# Schematic.net
KiCad netlist of a schematic drawn in EAGLE
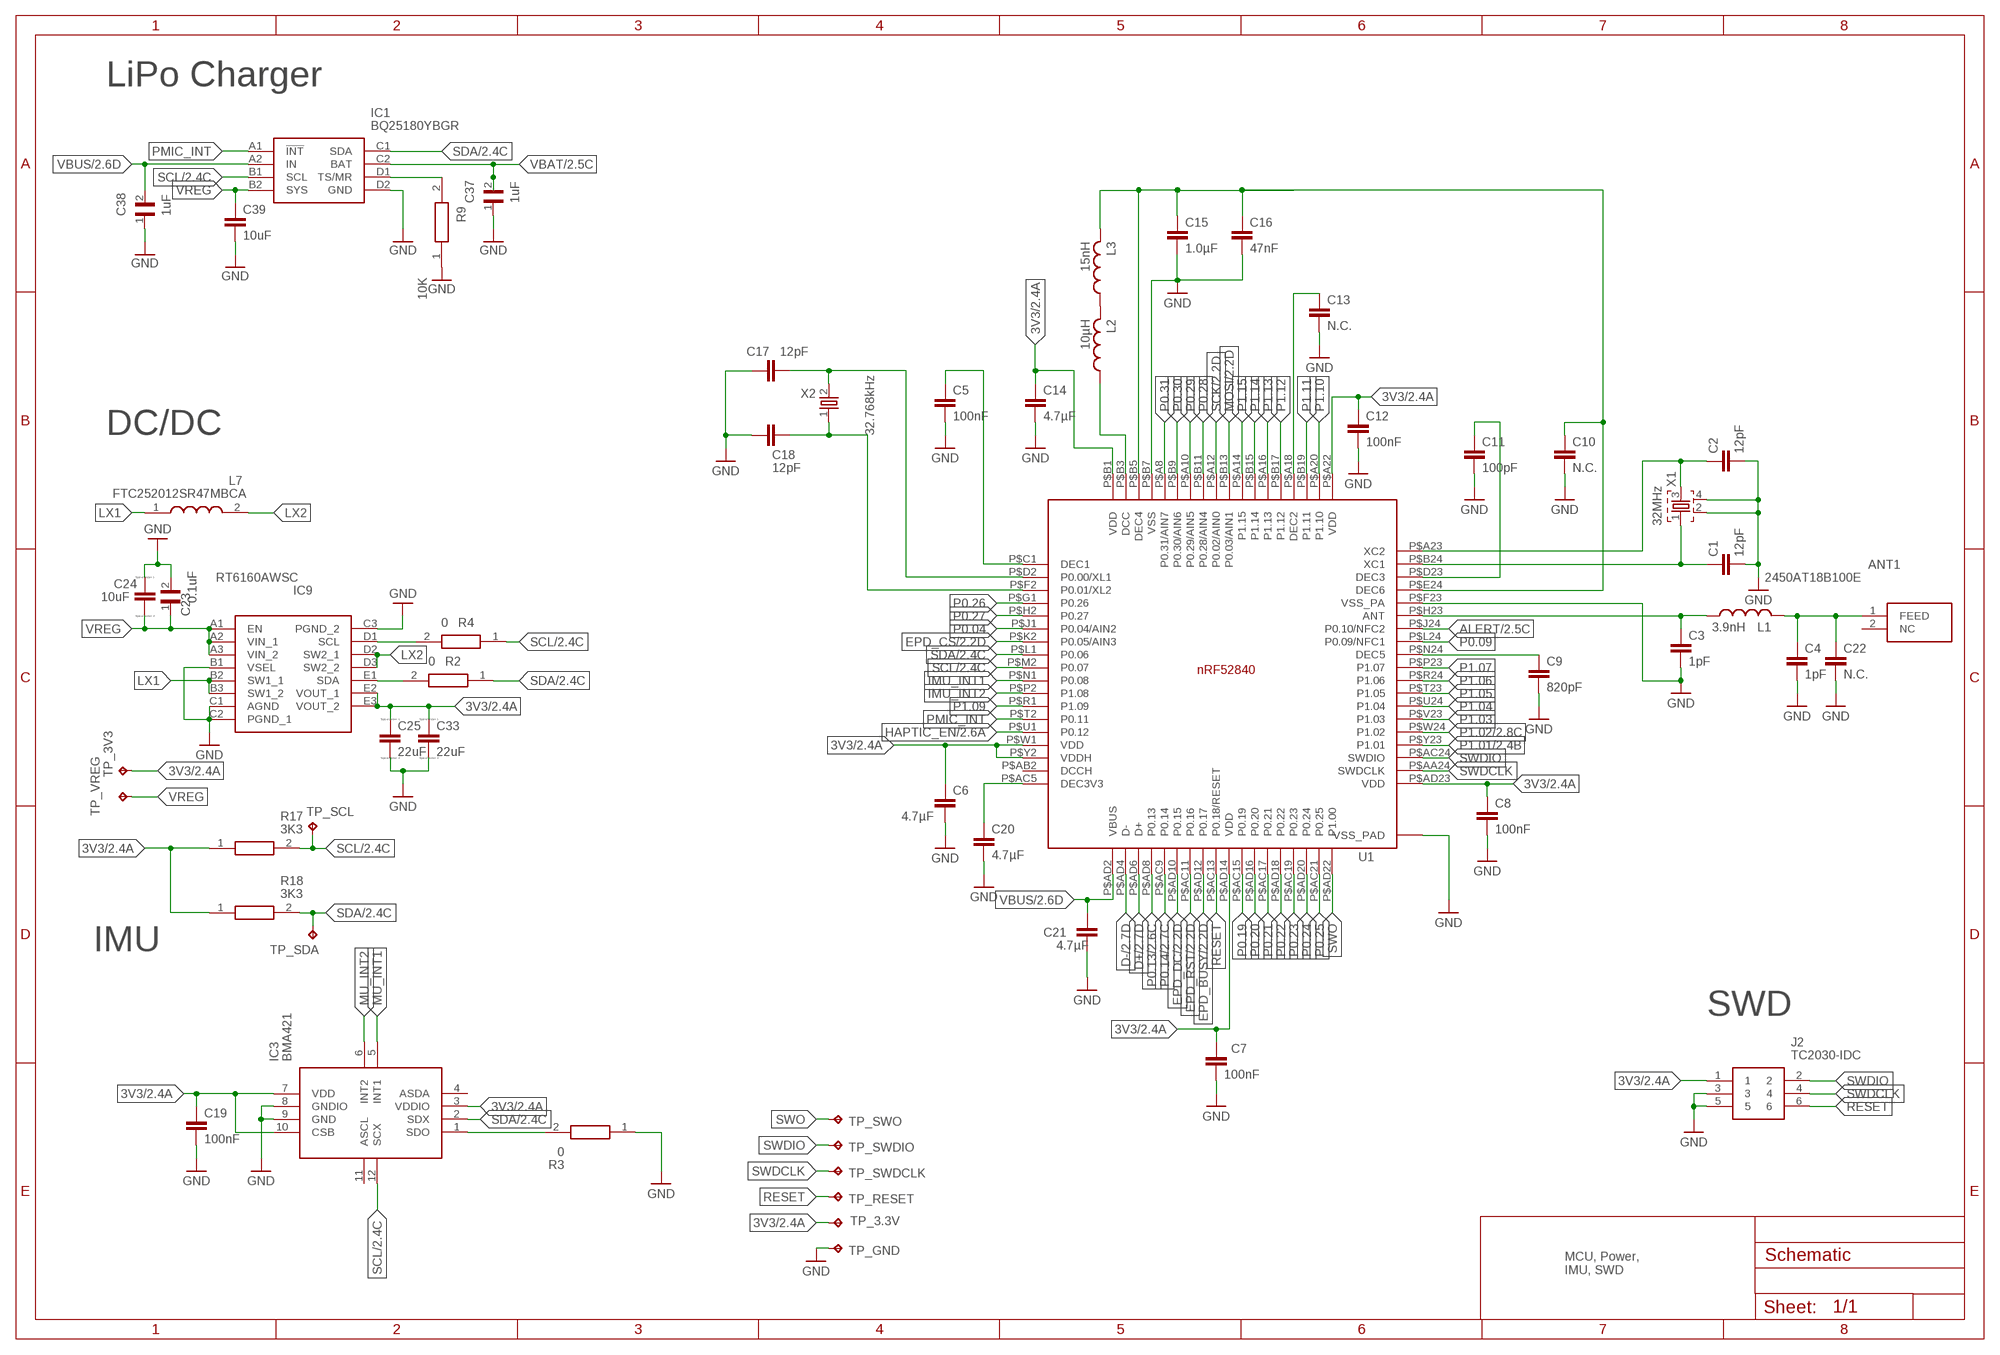
[diagram p0: schematic, sheet 1, part 1 of 2]
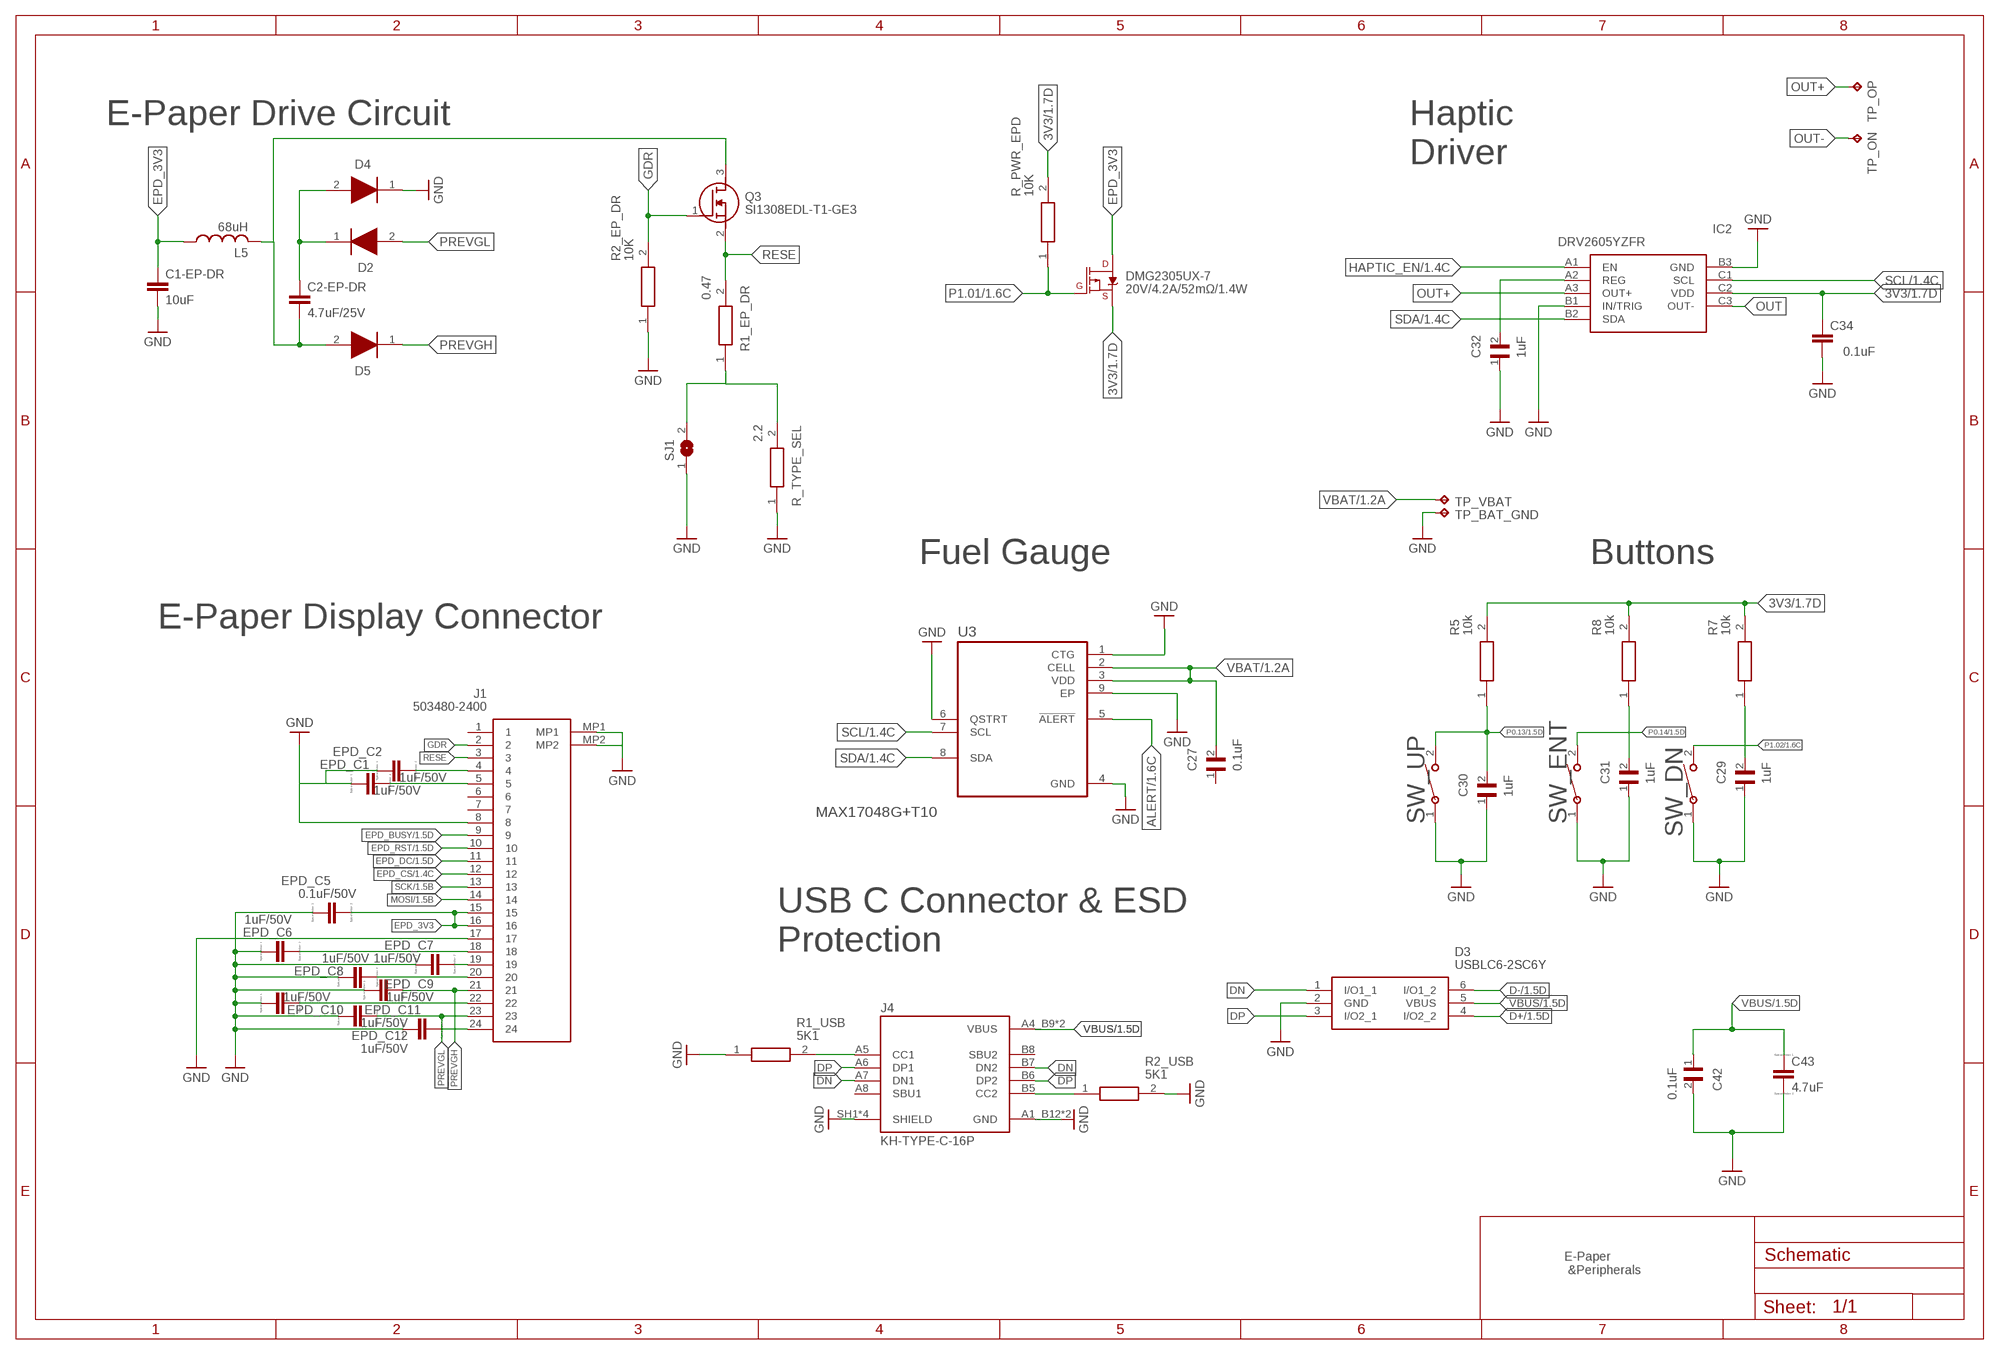
[diagram p1: schematic, sheet 1, part 2 of 2]

(export (version "E")
  (design (tool "Eeschema 10.0.6"))
  (components
    (comp (ref "ANT1")
      (value "2450AT18B100E")
      (footprint "eagle-import:2450AT18B100E_ANTC3216X140N")
      (fields (field (name "MOUSER_PART_NUMBER") "609-2450AT18B100E"))
      (libsource (lib "eagle-import") (part "2450AT18B100E_2450AT18B100E"))
    )
    (comp (ref "C1")
      (value "12pF")
      (footprint "eagle-import:NORDIC_NRF_3_RESC0201_L")
      (libsource (lib "eagle-import") (part "NORDIC_NRF_3_CAPACITOR_0201_L"))
    )
    (comp (ref "C1-EP-DR")
      (value "10uF")
      (footprint "eagle-import:NORDIC_NRF_3_RESC0201_L")
      (libsource (lib "eagle-import") (part "NORDIC_NRF_3_CAPACITOR_0201_L"))
    )
    (comp (ref "C2")
      (value "12pF")
      (footprint "eagle-import:NORDIC_NRF_3_RESC0201_L")
      (libsource (lib "eagle-import") (part "NORDIC_NRF_3_CAPACITOR_0201_L"))
    )
    (comp (ref "C2-EP-DR")
      (value "4.7uF/25V")
      (footprint "eagle-import:NORDIC_NRF_3_RESC0201_L")
      (libsource (lib "eagle-import") (part "NORDIC_NRF_3_CAPACITOR_0201_L"))
    )
    (comp (ref "C3")
      (value "1pF")
      (footprint "eagle-import:NORDIC_NRF_3_RESC0201_L")
      (libsource (lib "eagle-import") (part "NORDIC_NRF_3_CAPACITOR_0201_L"))
    )
    (comp (ref "C4")
      (value "1pF")
      (footprint "eagle-import:NORDIC_NRF_3_RESC0201_L")
      (libsource (lib "eagle-import") (part "NORDIC_NRF_3_CAPACITOR_0201_L"))
    )
    (comp (ref "C5")
      (value "100nF")
      (footprint "eagle-import:NORDIC_NRF_3_RESC0201_L")
      (libsource (lib "eagle-import") (part "NORDIC_NRF_3_CAPACITOR_0201_L"))
    )
    (comp (ref "C6")
      (value "4.7µF")
      (footprint "eagle-import:NORDIC_NRF_3_RESC0201_L")
      (libsource (lib "eagle-import") (part "NORDIC_NRF_3_CAPACITOR_0201_L"))
    )
    (comp (ref "C7")
      (value "100nF")
      (footprint "eagle-import:NORDIC_NRF_3_RESC0201_L")
      (libsource (lib "eagle-import") (part "NORDIC_NRF_3_CAPACITOR_0201_L"))
    )
    (comp (ref "C8")
      (value "100nF")
      (footprint "eagle-import:NORDIC_NRF_3_RESC0201_L")
      (libsource (lib "eagle-import") (part "NORDIC_NRF_3_CAPACITOR_0201_L"))
    )
    (comp (ref "C9")
      (value "820pF")
      (footprint "eagle-import:NORDIC_NRF_3_RESC0201_L")
      (libsource (lib "eagle-import") (part "NORDIC_NRF_3_CAPACITOR_0201_L"))
    )
    (comp (ref "C10")
      (value "N.C.")
      (footprint "eagle-import:NORDIC_NRF_3_RESC0201_L")
      (libsource (lib "eagle-import") (part "NORDIC_NRF_3_CAPACITOR_0201_L"))
    )
    (comp (ref "C11")
      (value "100pF")
      (footprint "eagle-import:NORDIC_NRF_3_RESC0201_L")
      (libsource (lib "eagle-import") (part "NORDIC_NRF_3_CAPACITOR_0201_L"))
    )
    (comp (ref "C12")
      (value "100nF")
      (footprint "eagle-import:NORDIC_NRF_3_RESC0201_L")
      (libsource (lib "eagle-import") (part "NORDIC_NRF_3_CAPACITOR_0201_L"))
    )
    (comp (ref "C13")
      (value "N.C.")
      (footprint "eagle-import:NORDIC_NRF_3_RESC0201_L")
      (libsource (lib "eagle-import") (part "NORDIC_NRF_3_CAPACITOR_0201_L"))
    )
    (comp (ref "C14")
      (value "4.7µF")
      (footprint "eagle-import:NORDIC_NRF_3_RESC0201_L")
      (libsource (lib "eagle-import") (part "NORDIC_NRF_3_CAPACITOR_0201_L"))
    )
    (comp (ref "C15")
      (value "1.0µF")
      (footprint "eagle-import:NORDIC_NRF_3_RESC0201_L")
      (libsource (lib "eagle-import") (part "NORDIC_NRF_3_CAPACITOR_0201_L"))
    )
    (comp (ref "C16")
      (value "47nF")
      (footprint "eagle-import:NORDIC_NRF_3_RESC0201_L")
      (libsource (lib "eagle-import") (part "NORDIC_NRF_3_CAPACITOR_0201_L"))
    )
    (comp (ref "C17")
      (value "12pF")
      (footprint "eagle-import:NORDIC_NRF_3_RESC0201_L")
      (libsource (lib "eagle-import") (part "NORDIC_NRF_3_CAPACITOR_0201_L"))
    )
    (comp (ref "C18")
      (value "12pF")
      (footprint "eagle-import:NORDIC_NRF_3_RESC0201_L")
      (libsource (lib "eagle-import") (part "NORDIC_NRF_3_CAPACITOR_0201_L"))
    )
    (comp (ref "C19")
      (value "100nF")
      (footprint "eagle-import:NORDIC_NRF_3_RESC0201_L")
      (libsource (lib "eagle-import") (part "NORDIC_NRF_3_CAPACITOR_0201_L"))
    )
    (comp (ref "C20")
      (value "4.7µF")
      (footprint "eagle-import:NORDIC_NRF_3_RESC0201_L")
      (libsource (lib "eagle-import") (part "NORDIC_NRF_3_CAPACITOR_0201_L"))
    )
    (comp (ref "C21")
      (value "4.7µF")
      (footprint "eagle-import:NORDIC_NRF_3_RESC0201_L")
      (libsource (lib "eagle-import") (part "NORDIC_NRF_3_CAPACITOR_0201_L"))
    )
    (comp (ref "C22")
      (value "N.C.")
      (footprint "eagle-import:NORDIC_NRF_3_RESC0201_L")
      (libsource (lib "eagle-import") (part "NORDIC_NRF_3_CAPACITOR_0201_L"))
    )
    (comp (ref "C23")
      (value "0.1uF")
      (footprint "eagle-import:GRM011R60J152KE01L_2_CAPC0201X13N")
      (fields (field (name "MF") "Murata") (field (name "MP") "GRM011R60J152KE01L"))
      (libsource (lib "eagle-import") (part "GRM011R60J152KE01L_2_GRM011R60J152KE01L"))
    )
    (comp (ref "C24")
      (value "10uF")
      (footprint "eagle-import:ESP32_C6_LIBRARY_1_ESP32_WROVER_EAGLE-LTSPICE_C0402")
      (libsource (lib "eagle-import") (part "ESP32_C6_LIBRARY_1_ESP32_WROVER_EAGLE-LTSPICE_CC0402"))
    )
    (comp (ref "C25")
      (value "22uF")
      (footprint "eagle-import:ESP32_C6_LIBRARY_1_ESP32_WROVER_EAGLE-LTSPICE_C0402")
      (libsource (lib "eagle-import") (part "ESP32_C6_LIBRARY_1_ESP32_WROVER_EAGLE-LTSPICE_CC0402"))
    )
    (comp (ref "C27")
      (value "0.1uF")
      (footprint "eagle-import:GRM011R60J152KE01L_2_CAPC0201X13N")
      (fields (field (name "MF") "Murata") (field (name "MP") "GRM011R60J152KE01L"))
      (libsource (lib "eagle-import") (part "GRM011R60J152KE01L_2_GRM011R60J152KE01L"))
    )
    (comp (ref "C29")
      (value "1uF")
      (footprint "eagle-import:GRM011R60J152KE01L_2_CAPC0201X13N")
      (fields (field (name "MF") "Murata") (field (name "MP") "GRM011R60J152KE01L"))
      (libsource (lib "eagle-import") (part "GRM011R60J152KE01L_2_GRM011R60J152KE01L"))
    )
    (comp (ref "C30")
      (value "1uF")
      (footprint "eagle-import:GRM011R60J152KE01L_2_CAPC0201X13N")
      (fields (field (name "MF") "Murata") (field (name "MP") "GRM011R60J152KE01L"))
      (libsource (lib "eagle-import") (part "GRM011R60J152KE01L_2_GRM011R60J152KE01L"))
    )
    (comp (ref "C31")
      (value "1uF")
      (footprint "eagle-import:GRM011R60J152KE01L_2_CAPC0201X13N")
      (fields (field (name "MF") "Murata") (field (name "MP") "GRM011R60J152KE01L"))
      (libsource (lib "eagle-import") (part "GRM011R60J152KE01L_2_GRM011R60J152KE01L"))
    )
    (comp (ref "C32")
      (value "1uF")
      (footprint "eagle-import:GRM011R60J152KE01L_2_CAPC0201X13N")
      (fields (field (name "MF") "Murata") (field (name "MP") "GRM011R60J152KE01L"))
      (libsource (lib "eagle-import") (part "GRM011R60J152KE01L_2_GRM011R60J152KE01L"))
    )
    (comp (ref "C33")
      (value "22uF")
      (footprint "eagle-import:ESP32_C6_LIBRARY_1_ESP32_WROVER_EAGLE-LTSPICE_C0402")
      (libsource (lib "eagle-import") (part "ESP32_C6_LIBRARY_1_ESP32_WROVER_EAGLE-LTSPICE_CC0402"))
    )
    (comp (ref "C34")
      (value "0.1uF")
      (footprint "eagle-import:NORDIC_NRF_3_RESC0201_L")
      (libsource (lib "eagle-import") (part "NORDIC_NRF_3_CAPACITOR_0201_L"))
    )
    (comp (ref "C37")
      (value "1uF")
      (footprint "eagle-import:GRM011R60J152KE01L_2_CAPC0201X13N")
      (fields (field (name "MF") "Murata") (field (name "MP") "GRM011R60J152KE01L"))
      (libsource (lib "eagle-import") (part "GRM011R60J152KE01L_2_GRM011R60J152KE01L"))
    )
    (comp (ref "C38")
      (value "1uF")
      (footprint "eagle-import:GRM011R60J152KE01L_2_CAPC0201X13N")
      (fields (field (name "MF") "Murata") (field (name "MP") "GRM011R60J152KE01L"))
      (libsource (lib "eagle-import") (part "GRM011R60J152KE01L_2_GRM011R60J152KE01L"))
    )
    (comp (ref "C39")
      (value "10uF")
      (footprint "eagle-import:NORDIC_NRF_3_RESC0201_L")
      (libsource (lib "eagle-import") (part "NORDIC_NRF_3_CAPACITOR_0201_L"))
    )
    (comp (ref "C42")
      (value "0.1uF")
      (footprint "eagle-import:GRM011R60J152KE01L_2_CAPC0201X13N")
      (fields (field (name "MF") "Murata") (field (name "MP") "GRM011R60J152KE01L"))
      (libsource (lib "eagle-import") (part "GRM011R60J152KE01L_2_GRM011R60J152KE01L"))
    )
    (comp (ref "C43")
      (value "4.7uF")
      (footprint "eagle-import:ESP32_C6_LIBRARY_1_ESP32_WROVER_EAGLE-LTSPICE_C0402")
      (libsource (lib "eagle-import") (part "ESP32_C6_LIBRARY_1_ESP32_WROVER_EAGLE-LTSPICE_CC0402"))
    )
    (comp (ref "D2")
      (value "ESP32_C6_LIBRARY_5_MBR0530")
      (footprint "eagle-import:ESP32_C6_LIBRARY_5_SOD3716X135N")
      (fields (field (name "MF") "ON Semiconductor") (field (name "MP") "MBR0530"))
      (libsource (lib "eagle-import") (part "ESP32_C6_LIBRARY_5_MBR0530"))
    )
    (comp (ref "D3")
      (value "USBLC6-2SC6Y")
      (footprint "eagle-import:ESP32_C6_LIBRARY_3_SOT95P280X145-6N")
      (fields (field (name "MF") "STMicroelectronics"))
      (libsource (lib "eagle-import") (part "ESP32_C6_LIBRARY_3_USBLC6-2SC6Y"))
    )
    (comp (ref "D4")
      (value "ESP32_C6_LIBRARY_5_MBR0530")
      (footprint "eagle-import:ESP32_C6_LIBRARY_5_SOD3716X135N")
      (fields (field (name "MF") "ON Semiconductor") (field (name "MP") "MBR0530"))
      (libsource (lib "eagle-import") (part "ESP32_C6_LIBRARY_5_MBR0530"))
    )
    (comp (ref "D5")
      (value "ESP32_C6_LIBRARY_5_MBR0530")
      (footprint "eagle-import:ESP32_C6_LIBRARY_5_SOD3716X135N")
      (fields (field (name "MF") "ON Semiconductor") (field (name "MP") "MBR0530"))
      (libsource (lib "eagle-import") (part "ESP32_C6_LIBRARY_5_MBR0530"))
    )
    (comp (ref "DMG2305UX-7")
      (value "20V/4.2A/52mΩ/1.4W")
      (footprint "eagle-import:ESP32_C6_LIBRARY_4_ESP32_C6_LIBRARY_4_ESP32_C6_LIBRARY_4_ESP32_C6_LIBRARY_4_ESP32_WROVER_SPARKFUN-DISCRETESEMI_SOT23-3")
      (libsource (lib "eagle-import") (part "ESP32_C6_LIBRARY_4_ESP32_WROVER_SPARKFUN-DISCRETESEMI_MOSFET_PCH-DMG2305UX-7"))
    )
    (comp (ref "EPD_C1")
      (value "1uF/50V")
      (footprint "eagle-import:ESP32_C6_LIBRARY_1_ESP32_WROVER_EAGLE-LTSPICE_C0402")
      (libsource (lib "eagle-import") (part "ESP32_C6_LIBRARY_1_ESP32_WROVER_EAGLE-LTSPICE_CC0402"))
    )
    (comp (ref "EPD_C2")
      (value "1uF/50V")
      (footprint "eagle-import:ESP32_C6_LIBRARY_1_ESP32_WROVER_EAGLE-LTSPICE_C0402")
      (libsource (lib "eagle-import") (part "ESP32_C6_LIBRARY_1_ESP32_WROVER_EAGLE-LTSPICE_CC0402"))
    )
    (comp (ref "EPD_C5")
      (value "0.1uF/50V")
      (footprint "eagle-import:ESP32_C6_LIBRARY_1_ESP32_WROVER_EAGLE-LTSPICE_C0402")
      (libsource (lib "eagle-import") (part "ESP32_C6_LIBRARY_1_ESP32_WROVER_EAGLE-LTSPICE_CC0402"))
    )
    (comp (ref "EPD_C6")
      (value "1uF/50V")
      (footprint "eagle-import:ESP32_C6_LIBRARY_1_ESP32_WROVER_EAGLE-LTSPICE_C0402")
      (libsource (lib "eagle-import") (part "ESP32_C6_LIBRARY_1_ESP32_WROVER_EAGLE-LTSPICE_CC0402"))
    )
    (comp (ref "EPD_C7")
      (value "1uF/50V")
      (footprint "eagle-import:ESP32_C6_LIBRARY_1_ESP32_WROVER_EAGLE-LTSPICE_C0402")
      (libsource (lib "eagle-import") (part "ESP32_C6_LIBRARY_1_ESP32_WROVER_EAGLE-LTSPICE_CC0402"))
    )
    (comp (ref "EPD_C8")
      (value "1uF/50V")
      (footprint "eagle-import:ESP32_C6_LIBRARY_1_ESP32_WROVER_EAGLE-LTSPICE_C0402")
      (libsource (lib "eagle-import") (part "ESP32_C6_LIBRARY_1_ESP32_WROVER_EAGLE-LTSPICE_CC0402"))
    )
    (comp (ref "EPD_C9")
      (value "1uF/50V")
      (footprint "eagle-import:ESP32_C6_LIBRARY_1_ESP32_WROVER_EAGLE-LTSPICE_C0402")
      (libsource (lib "eagle-import") (part "ESP32_C6_LIBRARY_1_ESP32_WROVER_EAGLE-LTSPICE_CC0402"))
    )
    (comp (ref "EPD_C10")
      (value "1uF/50V")
      (footprint "eagle-import:ESP32_C6_LIBRARY_1_ESP32_WROVER_EAGLE-LTSPICE_C0402")
      (libsource (lib "eagle-import") (part "ESP32_C6_LIBRARY_1_ESP32_WROVER_EAGLE-LTSPICE_CC0402"))
    )
    (comp (ref "EPD_C11")
      (value "1uF/50V")
      (footprint "eagle-import:ESP32_C6_LIBRARY_1_ESP32_WROVER_EAGLE-LTSPICE_C0402")
      (libsource (lib "eagle-import") (part "ESP32_C6_LIBRARY_1_ESP32_WROVER_EAGLE-LTSPICE_CC0402"))
    )
    (comp (ref "EPD_C12")
      (value "1uF/50V")
      (footprint "eagle-import:ESP32_C6_LIBRARY_1_ESP32_WROVER_EAGLE-LTSPICE_C0402")
      (libsource (lib "eagle-import") (part "ESP32_C6_LIBRARY_1_ESP32_WROVER_EAGLE-LTSPICE_CC0402"))
    )
    (comp (ref "IC1")
      (value "BQ25180YBGR")
      (footprint "eagle-import:BQ25180YBGR_BGA8C40P2X4_100X155X50")
      (fields (field (name "MOUSER_PART_NUMBER") "595-BQ25180YBGR"))
      (libsource (lib "eagle-import") (part "BQ25180YBGR_BQ25180YBGR"))
    )
    (comp (ref "IC2")
      (value "DRV2605YZFR")
      (footprint "eagle-import:DRV2605YZFR_BGA9C50P3X3_144X144X62")
      (libsource (lib "eagle-import") (part "DRV2605YZFR_DRV2605YZFR"))
    )
    (comp (ref "IC3")
      (value "BMA421")
      (footprint "eagle-import:BMA423_BMA423")
      (fields (field (name "ARROW_PART_NUMBER") "BMA423") (field (name "MOUSER_PART_NUMBER") "262-BMA423"))
      (libsource (lib "eagle-import") (part "BMA423_BMA423"))
    )
    (comp (ref "IC9")
      (value "RT6160AWSC")
      (footprint "eagle-import:RT6160AWSC_BGA15C40P3X5_140X230X60")
      (fields (field (name "MOUSER_PART_NUMBER") "835-RT6160AWSC"))
      (libsource (lib "eagle-import") (part "RT6160AWSC_RT6160AWSC"))
    )
    (comp (ref "J1")
      (value "503480-2400")
      (footprint "eagle-import:503480-2400_5034802400")
      (fields (field (name "MOUSER_PART_NUMBER") "538-503480-2400"))
      (libsource (lib "eagle-import") (part "503480-2400_503480-2400"))
    )
    (comp (ref "J2")
      (value "TC2030-IDC")
      (footprint "eagle-import:TC2030-IDC_TC2030IDC")
      (libsource (lib "eagle-import") (part "TC2030-IDC_TC2030-IDC"))
    )
    (comp (ref "J4")
      (value "KH-TYPE-C-16P")
      (footprint "eagle-import:KH-TYPE-C-16P_KINGHELM_KH-TYPE-C-16P")
      (fields (field (name "MF") "kinghelm"))
      (libsource (lib "eagle-import") (part "KH-TYPE-C-16P_KH-TYPE-C-16P"))
    )
    (comp (ref "L1")
      (value "3.9nH")
      (footprint "eagle-import:NORDIC_NRF_2_RESC0402_L")
      (libsource (lib "eagle-import") (part "NORDIC_NRF_2_INDUCTOR_0402_L"))
    )
    (comp (ref "L2")
      (value "10µH")
      (footprint "eagle-import:NORDIC_NRF_2_RESC0402_L")
      (libsource (lib "eagle-import") (part "NORDIC_NRF_2_INDUCTOR_0402_L"))
    )
    (comp (ref "L3")
      (value "15nH")
      (footprint "eagle-import:NORDIC_NRF_2_RESC0402_L")
      (libsource (lib "eagle-import") (part "NORDIC_NRF_2_INDUCTOR_0402_L"))
    )
    (comp (ref "L5")
      (value "68uH")
      (footprint "eagle-import:NORDIC_NRF_2_RESC0402_L")
      (libsource (lib "eagle-import") (part "NORDIC_NRF_2_INDUCTOR_0402_L"))
    )
    (comp (ref "L7")
      (value "FTC252012SR47MBCA")
      (footprint "eagle-import:MLP2016SR47MT0S1_INDC2016X100N")
      (libsource (lib "eagle-import") (part "MLP2016SR47MT0S1_FTC252012SR47MBCA"))
    )
    (comp (ref "Q3")
      (value "SI1308EDL-T1-GE3")
      (footprint "eagle-import:ESP32_C6_LIBRARY_6_SOT65P210X110-3N")
      (fields (field (name "MF") "Vishay Siliconix"))
      (libsource (lib "eagle-import") (part "ESP32_C6_LIBRARY_6_SI1308EDL-T1-GE3"))
    )
    (comp (ref "R1_EP_DR")
      (value "0.47")
      (footprint "eagle-import:ERA-1AEB3401C_0201")
      (libsource (lib "eagle-import") (part "ERA-1AEB3401C_CPF0201D7K68C1"))
    )
    (comp (ref "R1_USB")
      (value "5K1")
      (footprint "eagle-import:CPF0201D7K68C1_0201")
      (libsource (lib "eagle-import") (part "CPF0201D7K68C1_CPF0201D7K68C1"))
    )
    (comp (ref "R2")
      (value "0")
      (footprint "eagle-import:CPF0201D7K68C1_0201")
      (libsource (lib "eagle-import") (part "CPF0201D7K68C1_CPF0201D7K68C1"))
    )
    (comp (ref "R2_EP_DR")
      (value "10K")
      (footprint "eagle-import:ERA-1AEB3401C_0201")
      (libsource (lib "eagle-import") (part "ERA-1AEB3401C_CPF0201D7K68C1"))
    )
    (comp (ref "R2_USB")
      (value "5K1")
      (footprint "eagle-import:ERA-1AEB3401C_0201")
      (libsource (lib "eagle-import") (part "ERA-1AEB3401C_CPF0201D7K68C1"))
    )
    (comp (ref "R3")
      (value "0")
      (footprint "eagle-import:ERA-1AEB3401C_0201")
      (libsource (lib "eagle-import") (part "ERA-1AEB3401C_CPF0201D7K68C1"))
    )
    (comp (ref "R4")
      (value "0")
      (footprint "eagle-import:CPF0201D7K68C1_0201")
      (libsource (lib "eagle-import") (part "CPF0201D7K68C1_CPF0201D7K68C1"))
    )
    (comp (ref "R5")
      (value "10k")
      (footprint "eagle-import:CPF0201D7K68C1_0201")
      (libsource (lib "eagle-import") (part "CPF0201D7K68C1_CPF0201D7K68C1"))
    )
    (comp (ref "R7")
      (value "10k")
      (footprint "eagle-import:CPF0201D7K68C1_0201")
      (libsource (lib "eagle-import") (part "CPF0201D7K68C1_CPF0201D7K68C1"))
    )
    (comp (ref "R8")
      (value "10k")
      (footprint "eagle-import:CPF0201D7K68C1_0201")
      (libsource (lib "eagle-import") (part "CPF0201D7K68C1_CPF0201D7K68C1"))
    )
    (comp (ref "R9")
      (value "10K")
      (footprint "eagle-import:ERA-1AEB3401C_0201")
      (libsource (lib "eagle-import") (part "ERA-1AEB3401C_CPF0201D7K68C1"))
    )
    (comp (ref "R17")
      (value "3K3")
      (footprint "eagle-import:CPF0201D7K68C1_0201")
      (libsource (lib "eagle-import") (part "CPF0201D7K68C1_CPF0201D7K68C1"))
    )
    (comp (ref "R18")
      (value "3K3")
      (footprint "eagle-import:CPF0201D7K68C1_0201")
      (libsource (lib "eagle-import") (part "CPF0201D7K68C1_CPF0201D7K68C1"))
    )
    (comp (ref "R_PWR_EPD")
      (value "10K")
      (footprint "eagle-import:CPF0201D7K68C1_0201")
      (libsource (lib "eagle-import") (part "CPF0201D7K68C1_CPF0201D7K68C1"))
    )
    (comp (ref "R_TYPE_SEL")
      (value "2.2")
      (footprint "eagle-import:ERA-1AEB3401C_0201")
      (libsource (lib "eagle-import") (part "ERA-1AEB3401C_CPF0201D7K68C1"))
    )
    (comp (ref "SJ1")
      (value "ESP32_C6_LIBRARY_7_JUMPER_SJ")
      (footprint "eagle-import:ESP32_C6_LIBRARY_7_JUMPER_SJ")
      (libsource (lib "eagle-import") (part "ESP32_C6_LIBRARY_7_JUMPER_SJ"))
    )
    (comp (ref "SW_DN")
      (value "2025-10-22_07-23-44_LIBRARY_EVP-AKE31ASW_EVP-AKE31A_PAN")
      (footprint "eagle-import:2025-10-22_07-23-44_LIBRARY_SW_EVP-AKE31A_PAN")
      (fields
        (field (name "MANUFACTURER_PART_NUMBER") "EVP-AKE31A")
        (field (name "COPYRIGHT") "Copyright (C) 2025 Ultra Librarian. All rights reserved.")
      )
      (libsource (lib "eagle-import") (part "2025-10-22_07-23-44_LIBRARY_EVP-AKE31ASW_EVP-AKE31A_PAN"))
    )
    (comp (ref "SW_ENT")
      (value "2025-10-22_07-23-44_LIBRARY_EVP-AKE31ASW_EVP-AKE31A_PAN")
      (footprint "eagle-import:2025-10-22_07-23-44_LIBRARY_SW_EVP-AKE31A_PAN")
      (fields
        (field (name "MANUFACTURER_PART_NUMBER") "EVP-AKE31A")
        (field (name "COPYRIGHT") "Copyright (C) 2025 Ultra Librarian. All rights reserved.")
      )
      (libsource (lib "eagle-import") (part "2025-10-22_07-23-44_LIBRARY_EVP-AKE31ASW_EVP-AKE31A_PAN"))
    )
    (comp (ref "SW_UP")
      (value "2025-10-22_07-23-44_LIBRARY_EVP-AKE31ASW_EVP-AKE31A_PAN")
      (footprint "eagle-import:2025-10-22_07-23-44_LIBRARY_SW_EVP-AKE31A_PAN")
      (fields
        (field (name "MANUFACTURER_PART_NUMBER") "EVP-AKE31A")
        (field (name "COPYRIGHT") "Copyright (C) 2025 Ultra Librarian. All rights reserved.")
      )
      (libsource (lib "eagle-import") (part "2025-10-22_07-23-44_LIBRARY_EVP-AKE31ASW_EVP-AKE31A_PAN"))
    )
    (comp (ref "TP_3.3V")
      (value "HECTOR_WATCH_1_TPTP20R")
      (footprint "eagle-import:HECTOR_WATCH_1_TP20R")
      (libsource (lib "eagle-import") (part "HECTOR_WATCH_1_TPTP20R"))
    )
    (comp (ref "TP_3V3")
      (value "HECTOR_WATCH_1_TPTP20R")
      (footprint "eagle-import:HECTOR_WATCH_1_TP20R")
      (libsource (lib "eagle-import") (part "HECTOR_WATCH_1_TPTP20R"))
    )
    (comp (ref "TP_BAT_GND")
      (value "HECTOR_WATCH_1_TPTP20R")
      (footprint "eagle-import:HECTOR_WATCH_1_TP20R")
      (libsource (lib "eagle-import") (part "HECTOR_WATCH_1_TPTP20R"))
    )
    (comp (ref "TP_GND")
      (value "HECTOR_WATCH_1_TPTP20R")
      (footprint "eagle-import:HECTOR_WATCH_1_TP20R")
      (libsource (lib "eagle-import") (part "HECTOR_WATCH_1_TPTP20R"))
    )
    (comp (ref "TP_ON")
      (value "HECTOR_WATCH_1_TPTP20R")
      (footprint "eagle-import:HECTOR_WATCH_1_TP20R")
      (libsource (lib "eagle-import") (part "HECTOR_WATCH_1_TPTP20R"))
    )
    (comp (ref "TP_OP")
      (value "HECTOR_WATCH_1_TPTP20R")
      (footprint "eagle-import:HECTOR_WATCH_1_TP20R")
      (libsource (lib "eagle-import") (part "HECTOR_WATCH_1_TPTP20R"))
    )
    (comp (ref "TP_RESET")
      (value "HECTOR_WATCH_1_TPTP20R")
      (footprint "eagle-import:HECTOR_WATCH_1_TP20R")
      (libsource (lib "eagle-import") (part "HECTOR_WATCH_1_TPTP20R"))
    )
    (comp (ref "TP_SCL")
      (value "HECTOR_WATCH_1_TPTP20R")
      (footprint "eagle-import:HECTOR_WATCH_1_TP20R")
      (libsource (lib "eagle-import") (part "HECTOR_WATCH_1_TPTP20R"))
    )
    (comp (ref "TP_SDA")
      (value "HECTOR_WATCH_1_TPTP20R")
      (footprint "eagle-import:HECTOR_WATCH_1_TP20R")
      (libsource (lib "eagle-import") (part "HECTOR_WATCH_1_TPTP20R"))
    )
    (comp (ref "TP_SWDCLK")
      (value "HECTOR_WATCH_1_TPTP20R")
      (footprint "eagle-import:HECTOR_WATCH_1_TP20R")
      (libsource (lib "eagle-import") (part "HECTOR_WATCH_1_TPTP20R"))
    )
    (comp (ref "TP_SWDIO")
      (value "HECTOR_WATCH_1_TPTP20R")
      (footprint "eagle-import:HECTOR_WATCH_1_TP20R")
      (libsource (lib "eagle-import") (part "HECTOR_WATCH_1_TPTP20R"))
    )
    (comp (ref "TP_SWO")
      (value "HECTOR_WATCH_1_TPTP20R")
      (footprint "eagle-import:HECTOR_WATCH_1_TP20R")
      (libsource (lib "eagle-import") (part "HECTOR_WATCH_1_TPTP20R"))
    )
    (comp (ref "TP_VBAT")
      (value "HECTOR_WATCH_1_TPTP20R")
      (footprint "eagle-import:HECTOR_WATCH_1_TP20R")
      (libsource (lib "eagle-import") (part "HECTOR_WATCH_1_TPTP20R"))
    )
    (comp (ref "TP_VREG")
      (value "HECTOR_WATCH_1_TPTP20R")
      (footprint "eagle-import:HECTOR_WATCH_1_TP20R")
      (libsource (lib "eagle-import") (part "HECTOR_WATCH_1_TPTP20R"))
    )
    (comp (ref "U1")
      (value "NRF52840_QF")
      (footprint "eagle-import:NORDIC_NRF_4_AQFN50P700X700X85_HS-74N")
      (libsource (lib "eagle-import") (part "NORDIC_NRF_4_NRF52840_QF"))
    )
    (comp (ref "U3")
      (value "MAX17048G+T10")
      (footprint "eagle-import:ESP32_C6_LIBRARY_SON50P200X200X80-9N")
      (fields (field (name "MF") "Analog Devices"))
      (libsource (lib "eagle-import") (part "ESP32_C6_LIBRARY_MAX17048G+T10"))
    )
    (comp (ref "X1")
      (value "32MHz")
      (footprint "eagle-import:NORDIC_NRF_BT-XTAL_2016_N")
      (libsource (lib "eagle-import") (part "NORDIC_NRF_XTAL_32MHZ"))
    )
    (comp (ref "X2")
      (value "32.768kHz")
      (footprint "eagle-import:NORDIC_NRF_1_XTAL_3215_N")
      (libsource (lib "eagle-import") (part "NORDIC_NRF_1_XTAL_32KHZ"))
    )
  )
  (nets
    (net (code "1") (name "3V3{slash}1.7D") (class "Default")
      (node (ref "C34") (pin "1") (pinfunction "1_1") (pintype "passive"))
      (node (ref "DMG2305UX-7") (pin "2") (pinfunction "S_2") (pintype "bidirectional"))
      (node (ref "IC2") (pin "C2") (pinfunction "VDD_C2") (pintype "bidirectional"))
      (node (ref "R5") (pin "2") (pinfunction "2_2") (pintype "bidirectional"))
      (node (ref "R7") (pin "2") (pinfunction "2_2") (pintype "bidirectional"))
      (node (ref "R8") (pin "2") (pinfunction "2_2") (pintype "bidirectional"))
      (node (ref "R_PWR_EPD") (pin "2") (pinfunction "2_2") (pintype "bidirectional"))
    )
    (net (code "2") (name "3V3{slash}2.4A") (class "Default")
      (node (ref "C12") (pin "1") (pinfunction "1_1") (pintype "passive"))
      (node (ref "C14") (pin "1") (pinfunction "1_1") (pintype "passive"))
      (node (ref "C19") (pin "1") (pinfunction "1_1") (pintype "passive"))
      (node (ref "C25") (pin "1") (pinfunction "1_1") (pintype "passive"))
      (node (ref "C33") (pin "1") (pinfunction "1_1") (pintype "passive"))
      (node (ref "C6") (pin "1") (pinfunction "1_1") (pintype "passive"))
      (node (ref "C7") (pin "1") (pinfunction "1_1") (pintype "passive"))
      (node (ref "C8") (pin "1") (pinfunction "1_1") (pintype "passive"))
      (node (ref "IC3") (pin "10") (pinfunction "CSB_10") (pintype "bidirectional"))
      (node (ref "IC3") (pin "3") (pinfunction "VDDIO_3") (pintype "bidirectional"))
      (node (ref "IC3") (pin "7") (pinfunction "VDD_7") (pintype "bidirectional"))
      (node (ref "IC9") (pin "E2") (pinfunction "VOUT_1_E2") (pintype "bidirectional"))
      (node (ref "IC9") (pin "E3") (pinfunction "VOUT_2_E3") (pintype "bidirectional"))
      (node (ref "J2") (pin "1") (pinfunction "1_1") (pintype "bidirectional"))
      (node (ref "R17") (pin "1") (pinfunction "1_1") (pintype "bidirectional"))
      (node (ref "R18") (pin "1") (pinfunction "1_1") (pintype "bidirectional"))
      (node (ref "TP_3.3V") (pin "TP") (pinfunction "TP_TP") (pintype "input"))
      (node (ref "TP_3V3") (pin "TP") (pinfunction "TP_TP") (pintype "input"))
      (node (ref "U1") (pin "P$A22") (pinfunction "VDD_P$A22") (pintype "power_in"))
      (node (ref "U1") (pin "P$AD14") (pinfunction "VDD_P$AD14") (pintype "power_in"))
      (node (ref "U1") (pin "P$AD23") (pinfunction "VDD_P$AD23") (pintype "power_in"))
      (node (ref "U1") (pin "P$B1") (pinfunction "VDD_P$B1") (pintype "power_in"))
      (node (ref "U1") (pin "P$W1") (pinfunction "VDD_P$W1") (pintype "power_in"))
      (node (ref "U1") (pin "P$Y2") (pinfunction "VDDH_P$Y2") (pintype "power_in"))
    )
    (net (code "3") (name "ALERT{slash}1.6C") (class "Default")
      (node (ref "U3") (pin "5") (pinfunction "~{ALERT}_5") (pintype "output"))
    )
    (net (code "4") (name "ALERT{slash}2.5C") (class "Default")
      (node (ref "U1") (pin "P$J24") (pinfunction "P0.10/NFC2_P$J24") (pintype "bidirectional"))
    )
    (net (code "5") (name "D+{slash}1.5D") (class "Default")
      (node (ref "D3") (pin "4") (pinfunction "I/O2_2_4") (pintype "bidirectional"))
    )
    (net (code "6") (name "D+{slash}2.7D") (class "Default")
      (node (ref "U1") (pin "P$AD6") (pinfunction "D+_P$AD6") (pintype "bidirectional"))
    )
    (net (code "7") (name "D-{slash}1.5D") (class "Default")
      (node (ref "D3") (pin "6") (pinfunction "I/O1_2_6") (pintype "bidirectional"))
    )
    (net (code "8") (name "D-{slash}2.7D") (class "Default")
      (node (ref "U1") (pin "P$AD4") (pinfunction "D-_P$AD4") (pintype "bidirectional"))
    )
    (net (code "9") (name "DN") (class "Default")
      (node (ref "D3") (pin "1") (pinfunction "I/O1_1_1") (pintype "bidirectional"))
      (node (ref "J4") (pin "A7") (pinfunction "DN1_A7") (pintype "bidirectional"))
      (node (ref "J4") (pin "B7") (pinfunction "DN2_B7") (pintype "bidirectional"))
    )
    (net (code "10") (name "DP") (class "Default")
      (node (ref "D3") (pin "3") (pinfunction "I/O2_1_3") (pintype "bidirectional"))
      (node (ref "J4") (pin "A6") (pinfunction "DP1_A6") (pintype "bidirectional"))
      (node (ref "J4") (pin "B6") (pinfunction "DP2_B6") (pintype "bidirectional"))
    )
    (net (code "11") (name "EPD_3V3") (class "Default")
      (node (ref "C1-EP-DR") (pin "1") (pinfunction "1_1") (pintype "passive"))
      (node (ref "DMG2305UX-7") (pin "3") (pinfunction "D_3") (pintype "bidirectional"))
      (node (ref "EPD_C5") (pin "2") (pinfunction "2_2") (pintype "passive"))
      (node (ref "J1") (pin "15") (pinfunction "15_15") (pintype "bidirectional"))
      (node (ref "J1") (pin "16") (pinfunction "16_16") (pintype "bidirectional"))
      (node (ref "L5") (pin "1") (pinfunction "1_1") (pintype "passive"))
    )
    (net (code "12") (name "EPD_BUSY{slash}1.5D") (class "Default")
      (node (ref "J1") (pin "9") (pinfunction "9_9") (pintype "bidirectional"))
    )
    (net (code "13") (name "EPD_BUSY{slash}2.2D") (class "Default")
      (node (ref "U1") (pin "P$AD12") (pinfunction "P0.17_P$AD12") (pintype "bidirectional"))
    )
    (net (code "14") (name "EPD_CS{slash}1.4C") (class "Default")
      (node (ref "J1") (pin "12") (pinfunction "12_12") (pintype "bidirectional"))
    )
    (net (code "15") (name "EPD_CS{slash}2.2D") (class "Default")
      (node (ref "U1") (pin "P$K2") (pinfunction "P0.05/AIN3_P$K2") (pintype "bidirectional"))
    )
    (net (code "16") (name "EPD_DC{slash}1.5D") (class "Default")
      (node (ref "J1") (pin "11") (pinfunction "11_11") (pintype "bidirectional"))
    )
    (net (code "17") (name "EPD_DC{slash}2.2D") (class "Default")
      (node (ref "U1") (pin "P$AD10") (pinfunction "P0.15_P$AD10") (pintype "bidirectional"))
    )
    (net (code "18") (name "EPD_RST{slash}1.5D") (class "Default")
      (node (ref "J1") (pin "10") (pinfunction "10_10") (pintype "bidirectional"))
    )
    (net (code "19") (name "EPD_RST{slash}2.2D") (class "Default")
      (node (ref "U1") (pin "P$AC11") (pinfunction "P0.16_P$AC11") (pintype "bidirectional"))
    )
    (net (code "20") (name "GDR") (class "Default")
      (node (ref "J1") (pin "2") (pinfunction "2_2") (pintype "bidirectional"))
      (node (ref "Q3") (pin "1") (pinfunction "G_1") (pintype "bidirectional"))
      (node (ref "R2_EP_DR") (pin "2") (pinfunction "2_2") (pintype "bidirectional"))
    )
    (net (code "21") (name "GND") (class "Default")
      (node (ref "C1") (pin "2") (pinfunction "2_2") (pintype "passive"))
      (node (ref "C1-EP-DR") (pin "2") (pinfunction "2_2") (pintype "passive"))
      (node (ref "C10") (pin "2") (pinfunction "2_2") (pintype "passive"))
      (node (ref "C11") (pin "2") (pinfunction "2_2") (pintype "passive"))
      (node (ref "C12") (pin "2") (pinfunction "2_2") (pintype "passive"))
      (node (ref "C13") (pin "2") (pinfunction "2_2") (pintype "passive"))
      (node (ref "C14") (pin "2") (pinfunction "2_2") (pintype "passive"))
      (node (ref "C15") (pin "2") (pinfunction "2_2") (pintype "passive"))
      (node (ref "C16") (pin "2") (pinfunction "2_2") (pintype "passive"))
      (node (ref "C17") (pin "1") (pinfunction "1_1") (pintype "passive"))
      (node (ref "C18") (pin "2") (pinfunction "2_2") (pintype "passive"))
      (node (ref "C19") (pin "2") (pinfunction "2_2") (pintype "passive"))
      (node (ref "C2") (pin "2") (pinfunction "2_2") (pintype "passive"))
      (node (ref "C20") (pin "2") (pinfunction "2_2") (pintype "passive"))
      (node (ref "C21") (pin "2") (pinfunction "2_2") (pintype "passive"))
      (node (ref "C22") (pin "2") (pinfunction "2_2") (pintype "passive"))
      (node (ref "C23") (pin "2") (pinfunction "2_2") (pintype "passive"))
      (node (ref "C24") (pin "1") (pinfunction "1_1") (pintype "passive"))
      (node (ref "C25") (pin "2") (pinfunction "2_2") (pintype "passive"))
      (node (ref "C29") (pin "1") (pinfunction "1_1") (pintype "passive"))
      (node (ref "C3") (pin "2") (pinfunction "2_2") (pintype "passive"))
      (node (ref "C30") (pin "1") (pinfunction "1_1") (pintype "passive"))
      (node (ref "C31") (pin "1") (pinfunction "1_1") (pintype "passive"))
      (node (ref "C32") (pin "1") (pinfunction "1_1") (pintype "passive"))
      (node (ref "C33") (pin "2") (pinfunction "2_2") (pintype "passive"))
      (node (ref "C34") (pin "2") (pinfunction "2_2") (pintype "passive"))
      (node (ref "C37") (pin "1") (pinfunction "1_1") (pintype "passive"))
      (node (ref "C38") (pin "1") (pinfunction "1_1") (pintype "passive"))
      (node (ref "C39") (pin "2") (pinfunction "2_2") (pintype "passive"))
      (node (ref "C4") (pin "2") (pinfunction "2_2") (pintype "passive"))
      (node (ref "C42") (pin "2") (pinfunction "2_2") (pintype "passive"))
      (node (ref "C43") (pin "2") (pinfunction "2_2") (pintype "passive"))
      (node (ref "C5") (pin "2") (pinfunction "2_2") (pintype "passive"))
      (node (ref "C6") (pin "2") (pinfunction "2_2") (pintype "passive"))
      (node (ref "C7") (pin "2") (pinfunction "2_2") (pintype "passive"))
      (node (ref "C8") (pin "2") (pinfunction "2_2") (pintype "passive"))
      (node (ref "C9") (pin "2") (pinfunction "2_2") (pintype "passive"))
      (node (ref "D3") (pin "2") (pinfunction "GND_2") (pintype "bidirectional"))
      (node (ref "D4") (pin "1") (pinfunction "K_1") (pintype "bidirectional"))
      (node (ref "EPD_C10") (pin "1") (pinfunction "1_1") (pintype "passive"))
      (node (ref "EPD_C11") (pin "1") (pinfunction "1_1") (pintype "passive"))
      (node (ref "EPD_C12") (pin "1") (pinfunction "1_1") (pintype "passive"))
      (node (ref "EPD_C5") (pin "1") (pinfunction "1_1") (pintype "passive"))
      (node (ref "EPD_C6") (pin "1") (pinfunction "1_1") (pintype "passive"))
      (node (ref "EPD_C7") (pin "1") (pinfunction "1_1") (pintype "passive"))
      (node (ref "EPD_C8") (pin "1") (pinfunction "1_1") (pintype "passive"))
      (node (ref "EPD_C9") (pin "1") (pinfunction "1_1") (pintype "passive"))
      (node (ref "IC1") (pin "D2") (pinfunction "GND_D2") (pintype "bidirectional"))
      (node (ref "IC2") (pin "B1") (pinfunction "IN/TRIG_B1") (pintype "bidirectional"))
      (node (ref "IC2") (pin "B3") (pinfunction "GND_B3") (pintype "bidirectional"))
      (node (ref "IC3") (pin "8") (pinfunction "GNDIO_8") (pintype "bidirectional"))
      (node (ref "IC3") (pin "9") (pinfunction "GND_9") (pintype "bidirectional"))
      (node (ref "IC9") (pin "B1") (pinfunction "VSEL_B1") (pintype "bidirectional"))
      (node (ref "IC9") (pin "C1") (pinfunction "AGND_C1") (pintype "bidirectional"))
      (node (ref "IC9") (pin "C2") (pinfunction "PGND_1_C2") (pintype "bidirectional"))
      (node (ref "IC9") (pin "C3") (pinfunction "PGND_2_C3") (pintype "bidirectional"))
      (node (ref "J1") (pin "17") (pinfunction "17_17") (pintype "bidirectional"))
      (node (ref "J1") (pin "8") (pinfunction "8_8") (pintype "bidirectional"))
      (node (ref "J1") (pin "MP1") (pinfunction "MP1_MP1") (pintype "bidirectional"))
      (node (ref "J2") (pin "3") (pinfunction "3_3") (pintype "bidirectional"))
      (node (ref "J2") (pin "5") (pinfunction "5_5") (pintype "bidirectional"))
      (node (ref "J4") (pin "A12_B1") (pinfunction "GND_A12_B1") (pintype "power_in"))
      (node (ref "J4") (pin "A1_B12") (pinfunction "GND_A1_B12") (pintype "power_in"))
      (node (ref "J4") (pin "SH1") (pinfunction "SHIELD_SH1") (pintype "passive"))
      (node (ref "J4") (pin "SH2") (pinfunction "SHIELD_SH2") (pintype "passive"))
      (node (ref "J4") (pin "SH3") (pinfunction "SHIELD_SH3") (pintype "passive"))
      (node (ref "J4") (pin "SH4") (pinfunction "SHIELD_SH4") (pintype "passive"))
      (node (ref "R1_USB") (pin "1") (pinfunction "1_1") (pintype "bidirectional"))
      (node (ref "R2_EP_DR") (pin "1") (pinfunction "1_1") (pintype "bidirectional"))
      (node (ref "R2_USB") (pin "2") (pinfunction "2_2") (pintype "bidirectional"))
      (node (ref "R3") (pin "1") (pinfunction "1_1") (pintype "bidirectional"))
      (node (ref "R9") (pin "1") (pinfunction "1_1") (pintype "bidirectional"))
      (node (ref "R_TYPE_SEL") (pin "1") (pinfunction "1_1") (pintype "bidirectional"))
      (node (ref "SJ1") (pin "1") (pinfunction "1_1") (pintype "passive"))
      (node (ref "SW_DN") (pin "1") (pinfunction "1_1") (pintype "passive"))
      (node (ref "SW_ENT") (pin "1") (pinfunction "1_1") (pintype "passive"))
      (node (ref "SW_UP") (pin "1") (pinfunction "1_1") (pintype "passive"))
      (node (ref "TP_BAT_GND") (pin "TP") (pinfunction "TP_TP") (pintype "input"))
      (node (ref "TP_GND") (pin "TP") (pinfunction "TP_TP") (pintype "input"))
      (node (ref "U1") (pin "P$74") (pinfunction "VSS_PAD_P$74") (pintype "bidirectional"))
      (node (ref "U1") (pin "P$75") (pinfunction "VSS_PAD_P$75") (pintype "bidirectional"))
      (node (ref "U1") (pin "P$76") (pinfunction "VSS_PAD_P$76") (pintype "bidirectional"))
      (node (ref "U1") (pin "P$77") (pinfunction "VSS_PAD_P$77") (pintype "bidirectional"))
      (node (ref "U1") (pin "P$78") (pinfunction "VSS_PAD_P$78") (pintype "bidirectional"))
      (node (ref "U1") (pin "P$79") (pinfunction "VSS_PAD_P$79") (pintype "bidirectional"))
      (node (ref "U1") (pin "P$80") (pinfunction "VSS_PAD_P$80") (pintype "bidirectional"))
      (node (ref "U1") (pin "P$81") (pinfunction "VSS_PAD_P$81") (pintype "bidirectional"))
      (node (ref "U1") (pin "P$82") (pinfunction "VSS_PAD_P$82") (pintype "bidirectional"))
      (node (ref "U1") (pin "P$83") (pinfunction "VSS_PAD_P$83") (pintype "bidirectional"))
      (node (ref "U1") (pin "P$84") (pinfunction "VSS_PAD_P$84") (pintype "bidirectional"))
      (node (ref "U1") (pin "P$85") (pinfunction "VSS_PAD_P$85") (pintype "bidirectional"))
      (node (ref "U1") (pin "P$86") (pinfunction "VSS_PAD_P$86") (pintype "bidirectional"))
      (node (ref "U1") (pin "P$87") (pinfunction "VSS_PAD_P$87") (pintype "bidirectional"))
      (node (ref "U1") (pin "P$88") (pinfunction "VSS_PAD_P$88") (pintype "bidirectional"))
      (node (ref "U1") (pin "P$89") (pinfunction "VSS_PAD_P$89") (pintype "bidirectional"))
      (node (ref "U1") (pin "P$90") (pinfunction "VSS_PAD_P$90") (pintype "bidirectional"))
      (node (ref "U1") (pin "P$B7") (pinfunction "VSS_P$B7") (pintype "power_in"))
      (node (ref "U1") (pin "P$F23") (pinfunction "VSS_PA_P$F23") (pintype "bidirectional"))
      (node (ref "U3") (pin "1") (pinfunction "CTG_1") (pintype "power_in"))
      (node (ref "U3") (pin "4") (pinfunction "GND_4") (pintype "power_in"))
      (node (ref "U3") (pin "6") (pinfunction "QSTRT_6") (pintype "input"))
      (node (ref "U3") (pin "9") (pinfunction "EP_9") (pintype "power_in"))
      (node (ref "X1") (pin "2") (pinfunction "2_2") (pintype "passive"))
      (node (ref "X1") (pin "4") (pinfunction "4_4") (pintype "passive"))
    )
    (net (code "22") (name "HAPTIC_EN{slash}1.4C") (class "Default")
      (node (ref "IC2") (pin "A1") (pinfunction "EN_A1") (pintype "bidirectional"))
    )
    (net (code "23") (name "HAPTIC_EN{slash}2.6A") (class "Default")
      (node (ref "U1") (pin "P$U1") (pinfunction "P0.12_P$U1") (pintype "bidirectional"))
    )
    (net (code "24") (name "IMU_INT1") (class "Default")
      (node (ref "U1") (pin "P$N1") (pinfunction "P0.08_P$N1") (pintype "bidirectional"))
    )
    (net (code "25") (name "IMU_INT2") (class "Default")
      (node (ref "U1") (pin "P$P2") (pinfunction "P1.08_P$P2") (pintype "bidirectional"))
    )
    (net (code "26") (name "LX1") (class "Default")
      (node (ref "IC9") (pin "B2") (pinfunction "SW1_1_B2") (pintype "bidirectional"))
      (node (ref "IC9") (pin "B3") (pinfunction "SW1_2_B3") (pintype "bidirectional"))
      (node (ref "L7") (pin "1") (pinfunction "1_1") (pintype "bidirectional"))
    )
    (net (code "27") (name "LX2") (class "Default")
      (node (ref "IC9") (pin "D2") (pinfunction "SW2_1_D2") (pintype "bidirectional"))
      (node (ref "IC9") (pin "D3") (pinfunction "SW2_2_D3") (pintype "bidirectional"))
      (node (ref "L7") (pin "2") (pinfunction "2_2") (pintype "bidirectional"))
    )
    (net (code "28") (name "MOSI{slash}1.5B") (class "Default")
      (node (ref "J1") (pin "14") (pinfunction "14_14") (pintype "bidirectional"))
    )
    (net (code "29") (name "MOSI{slash}2.2D") (class "Default")
      (node (ref "U1") (pin "P$B13") (pinfunction "P0.03/AIN1_P$B13") (pintype "bidirectional"))
    )
    (net (code "30") (name "MU_INT1") (class "Default")
      (node (ref "IC3") (pin "5") (pinfunction "INT1_5") (pintype "bidirectional"))
    )
    (net (code "31") (name "MU_INT2") (class "Default")
      (node (ref "IC3") (pin "6") (pinfunction "INT2_6") (pintype "bidirectional"))
    )
    (net (code "32") (name "Net-(ANT1-FEED)") (class "Default")
      (node (ref "ANT1") (pin "1") (pinfunction "FEED_1") (pintype "input"))
      (node (ref "C22") (pin "1") (pinfunction "1_1") (pintype "passive"))
      (node (ref "C4") (pin "1") (pinfunction "1_1") (pintype "passive"))
      (node (ref "L1") (pin "2") (pinfunction "2_2") (pintype "passive"))
    )
    (net (code "33") (name "Net-(C29-Pad2)") (class "Default")
      (node (ref "C29") (pin "2") (pinfunction "2_2") (pintype "passive"))
      (node (ref "R7") (pin "1") (pinfunction "1_1") (pintype "bidirectional"))
    )
    (net (code "34") (name "Net-(C31-Pad2)") (class "Default")
      (node (ref "C31") (pin "2") (pinfunction "2_2") (pintype "passive"))
      (node (ref "R8") (pin "1") (pinfunction "1_1") (pintype "bidirectional"))
    )
    (net (code "35") (name "Net-(D2-K)") (class "Default")
      (node (ref "C2-EP-DR") (pin "1") (pinfunction "1_1") (pintype "passive"))
      (node (ref "D2") (pin "1") (pinfunction "K_1") (pintype "bidirectional"))
      (node (ref "D4") (pin "2") (pinfunction "A_2") (pintype "bidirectional"))
    )
    (net (code "36") (name "Net-(D5-A)") (class "Default")
      (node (ref "C2-EP-DR") (pin "2") (pinfunction "2_2") (pintype "passive"))
      (node (ref "D5") (pin "2") (pinfunction "A_2") (pintype "bidirectional"))
      (node (ref "L5") (pin "2") (pinfunction "2_2") (pintype "passive"))
      (node (ref "Q3") (pin "3") (pinfunction "D_3") (pintype "bidirectional"))
    )
    (net (code "37") (name "Net-(EPD_C1-Pad2)") (class "Default")
      (node (ref "EPD_C1") (pin "2") (pinfunction "2_2") (pintype "passive"))
      (node (ref "J1") (pin "5") (pinfunction "5_5") (pintype "bidirectional"))
    )
    (net (code "38") (name "Net-(EPD_C2-Pad2)") (class "Default")
      (node (ref "EPD_C2") (pin "2") (pinfunction "2_2") (pintype "passive"))
      (node (ref "J1") (pin "4") (pinfunction "4_4") (pintype "bidirectional"))
    )
    (net (code "39") (name "Net-(EPD_C6-Pad2)") (class "Default")
      (node (ref "EPD_C6") (pin "2") (pinfunction "2_2") (pintype "passive"))
      (node (ref "J1") (pin "18") (pinfunction "18_18") (pintype "bidirectional"))
    )
    (net (code "40") (name "Net-(EPD_C7-Pad2)") (class "Default")
      (node (ref "EPD_C7") (pin "2") (pinfunction "2_2") (pintype "passive"))
      (node (ref "J1") (pin "19") (pinfunction "19_19") (pintype "bidirectional"))
    )
    (net (code "41") (name "Net-(EPD_C8-Pad2)") (class "Default")
      (node (ref "EPD_C8") (pin "2") (pinfunction "2_2") (pintype "passive"))
      (node (ref "J1") (pin "20") (pinfunction "20_20") (pintype "bidirectional"))
    )
    (net (code "42") (name "Net-(EPD_C10-Pad2)") (class "Default")
      (node (ref "EPD_C10") (pin "2") (pinfunction "2_2") (pintype "passive"))
      (node (ref "J1") (pin "22") (pinfunction "22_22") (pintype "bidirectional"))
    )
    (net (code "43") (name "Net-(EPD_C12-Pad2)") (class "Default")
      (node (ref "EPD_C12") (pin "2") (pinfunction "2_2") (pintype "passive"))
      (node (ref "J1") (pin "24") (pinfunction "24_24") (pintype "bidirectional"))
    )
    (net (code "44") (name "Net-(IC1-TS{slash}MR)") (class "Default")
      (node (ref "IC1") (pin "D1") (pinfunction "TS/MR_D1") (pintype "bidirectional"))
      (node (ref "R9") (pin "2") (pinfunction "2_2") (pintype "bidirectional"))
    )
    (net (code "45") (name "Net-(IC2-REG)") (class "Default")
      (node (ref "C32") (pin "2") (pinfunction "2_2") (pintype "passive"))
      (node (ref "IC2") (pin "A2") (pinfunction "REG_A2") (pintype "bidirectional"))
    )
    (net (code "46") (name "Net-(IC3-SDO)") (class "Default")
      (node (ref "IC3") (pin "1") (pinfunction "SDO_1") (pintype "bidirectional"))
      (node (ref "R3") (pin "2") (pinfunction "2_2") (pintype "bidirectional"))
    )
    (net (code "47") (name "Net-(IC9-SCL)") (class "Default")
      (node (ref "IC9") (pin "D1") (pinfunction "SCL_D1") (pintype "bidirectional"))
      (node (ref "R4") (pin "2") (pinfunction "2_2") (pintype "bidirectional"))
    )
    (net (code "48") (name "Net-(IC9-SDA)") (class "Default")
      (node (ref "IC9") (pin "E1") (pinfunction "SDA_E1") (pintype "bidirectional"))
      (node (ref "R2") (pin "2") (pinfunction "2_2") (pintype "bidirectional"))
    )
    (net (code "49") (name "Net-(J4-CC1)") (class "Default")
      (node (ref "J4") (pin "A5") (pinfunction "CC1_A5") (pintype "bidirectional"))
      (node (ref "R1_USB") (pin "2") (pinfunction "2_2") (pintype "bidirectional"))
    )
    (net (code "50") (name "Net-(J4-CC2)") (class "Default")
      (node (ref "J4") (pin "B5") (pinfunction "CC2_B5") (pintype "bidirectional"))
      (node (ref "R2_USB") (pin "1") (pinfunction "1_1") (pintype "bidirectional"))
    )
    (net (code "51") (name "Net-(L2-Pad2)") (class "Default")
      (node (ref "L2") (pin "2") (pinfunction "2_2") (pintype "passive"))
      (node (ref "L3") (pin "1") (pinfunction "1_1") (pintype "passive"))
    )
    (net (code "52") (name "Net-(R1_EP_DR-Pad1)") (class "Default")
      (node (ref "R1_EP_DR") (pin "1") (pinfunction "1_1") (pintype "bidirectional"))
      (node (ref "R_TYPE_SEL") (pin "2") (pinfunction "2_2") (pintype "bidirectional"))
      (node (ref "SJ1") (pin "2") (pinfunction "2_2") (pintype "passive"))
    )
    (net (code "53") (name "Net-(U1-ANT)") (class "Default")
      (node (ref "C3") (pin "1") (pinfunction "1_1") (pintype "passive"))
      (node (ref "L1") (pin "1") (pinfunction "1_1") (pintype "passive"))
      (node (ref "U1") (pin "P$H23") (pinfunction "ANT_P$H23") (pintype "bidirectional"))
    )
    (net (code "54") (name "Net-(U1-DCC)") (class "Default")
      (node (ref "L2") (pin "1") (pinfunction "1_1") (pintype "passive"))
      (node (ref "U1") (pin "P$B3") (pinfunction "DCC_P$B3") (pintype "output"))
    )
    (net (code "55") (name "Net-(U1-DEC1)") (class "Default")
      (node (ref "C5") (pin "1") (pinfunction "1_1") (pintype "passive"))
      (node (ref "U1") (pin "P$C1") (pinfunction "DEC1_P$C1") (pintype "power_in"))
    )
    (net (code "56") (name "Net-(U1-DEC2)") (class "Default")
      (node (ref "C13") (pin "1") (pinfunction "1_1") (pintype "passive"))
      (node (ref "U1") (pin "P$A18") (pinfunction "DEC2_P$A18") (pintype "bidirectional"))
    )
    (net (code "57") (name "Net-(U1-DEC3)") (class "Default")
      (node (ref "C11") (pin "1") (pinfunction "1_1") (pintype "passive"))
      (node (ref "U1") (pin "P$D23") (pinfunction "DEC3_P$D23") (pintype "bidirectional"))
    )
    (net (code "58") (name "Net-(U1-DEC3V3)") (class "Default")
      (node (ref "C20") (pin "1") (pinfunction "1_1") (pintype "passive"))
      (node (ref "U1") (pin "P$AC5") (pinfunction "DEC3V3_P$AC5") (pintype "bidirectional"))
    )
    (net (code "59") (name "Net-(U1-DEC4)") (class "Default")
      (node (ref "C10") (pin "1") (pinfunction "1_1") (pintype "passive"))
      (node (ref "C15") (pin "1") (pinfunction "1_1") (pintype "passive"))
      (node (ref "C16") (pin "1") (pinfunction "1_1") (pintype "passive"))
      (node (ref "L3") (pin "2") (pinfunction "2_2") (pintype "passive"))
      (node (ref "U1") (pin "P$B5") (pinfunction "DEC4_P$B5") (pintype "power_in"))
      (node (ref "U1") (pin "P$E24") (pinfunction "DEC6_P$E24") (pintype "bidirectional"))
    )
    (net (code "60") (name "Net-(U1-DEC5)") (class "Default")
      (node (ref "C9") (pin "1") (pinfunction "1_1") (pintype "passive"))
      (node (ref "U1") (pin "P$N24") (pinfunction "DEC5_P$N24") (pintype "bidirectional"))
    )
    (net (code "61") (name "Net-(U1-P0.00{slash}XL1)") (class "Default")
      (node (ref "C17") (pin "2") (pinfunction "2_2") (pintype "passive"))
      (node (ref "U1") (pin "P$D2") (pinfunction "P0.00/XL1_P$D2") (pintype "bidirectional"))
      (node (ref "X2") (pin "2") (pinfunction "2_2") (pintype "passive"))
    )
    (net (code "62") (name "Net-(U1-P0.01{slash}XL2)") (class "Default")
      (node (ref "C18") (pin "1") (pinfunction "1_1") (pintype "passive"))
      (node (ref "U1") (pin "P$F2") (pinfunction "P0.01/XL2_P$F2") (pintype "bidirectional"))
      (node (ref "X2") (pin "1") (pinfunction "1_1") (pintype "passive"))
    )
    (net (code "63") (name "Net-(U1-XC1)") (class "Default")
      (node (ref "C1") (pin "1") (pinfunction "1_1") (pintype "passive"))
      (node (ref "U1") (pin "P$B24") (pinfunction "XC1_P$B24") (pintype "input"))
      (node (ref "X1") (pin "1") (pinfunction "1_1") (pintype "passive"))
    )
    (net (code "64") (name "Net-(U1-XC2)") (class "Default")
      (node (ref "C2") (pin "1") (pinfunction "1_1") (pintype "passive"))
      (node (ref "U1") (pin "P$A23") (pinfunction "XC2_P$A23") (pintype "output"))
      (node (ref "X1") (pin "3") (pinfunction "3_3") (pintype "passive"))
    )
    (net (code "65") (name "OUT") (class "Default")
      (node (ref "IC2") (pin "C3") (pinfunction "OUT-_C3") (pintype "bidirectional"))
    )
    (net (code "66") (name "OUT+") (class "Default")
      (node (ref "IC2") (pin "A3") (pinfunction "OUT+_A3") (pintype "bidirectional"))
      (node (ref "TP_OP") (pin "TP") (pinfunction "TP_TP") (pintype "input"))
    )
    (net (code "67") (name "OUT-") (class "Default")
      (node (ref "TP_ON") (pin "TP") (pinfunction "TP_TP") (pintype "input"))
    )
    (net (code "68") (name "P0.04") (class "Default")
      (node (ref "U1") (pin "P$J1") (pinfunction "P0.04/AIN2_P$J1") (pintype "bidirectional"))
    )
    (net (code "69") (name "P0.09") (class "Default")
      (node (ref "U1") (pin "P$L24") (pinfunction "P0.09/NFC1_P$L24") (pintype "bidirectional"))
    )
    (net (code "70") (name "P0.13{slash}1.5D") (class "Default")
      (node (ref "C30") (pin "2") (pinfunction "2_2") (pintype "passive"))
      (node (ref "R5") (pin "1") (pinfunction "1_1") (pintype "bidirectional"))
      (node (ref "SW_UP") (pin "2") (pinfunction "2_2") (pintype "passive"))
    )
    (net (code "71") (name "P0.13{slash}2.6C") (class "Default")
      (node (ref "U1") (pin "P$AD8") (pinfunction "P0.13_P$AD8") (pintype "bidirectional"))
    )
    (net (code "72") (name "P0.14{slash}1.5D") (class "Default")
      (node (ref "SW_ENT") (pin "2") (pinfunction "2_2") (pintype "passive"))
    )
    (net (code "73") (name "P0.14{slash}2.7C") (class "Default")
      (node (ref "U1") (pin "P$AC9") (pinfunction "P0.14_P$AC9") (pintype "bidirectional"))
    )
    (net (code "74") (name "P0.19") (class "Default")
      (node (ref "U1") (pin "P$AC15") (pinfunction "P0.19_P$AC15") (pintype "bidirectional"))
    )
    (net (code "75") (name "P0.20") (class "Default")
      (node (ref "U1") (pin "P$AD16") (pinfunction "P0.20_P$AD16") (pintype "bidirectional"))
    )
    (net (code "76") (name "P0.21") (class "Default")
      (node (ref "U1") (pin "P$AC17") (pinfunction "P0.21_P$AC17") (pintype "bidirectional"))
    )
    (net (code "77") (name "P0.22") (class "Default")
      (node (ref "U1") (pin "P$AD18") (pinfunction "P0.22_P$AD18") (pintype "bidirectional"))
    )
    (net (code "78") (name "P0.23") (class "Default")
      (node (ref "U1") (pin "P$AC19") (pinfunction "P0.23_P$AC19") (pintype "bidirectional"))
    )
    (net (code "79") (name "P0.24") (class "Default")
      (node (ref "U1") (pin "P$AD20") (pinfunction "P0.24_P$AD20") (pintype "bidirectional"))
    )
    (net (code "80") (name "P0.25") (class "Default")
      (node (ref "U1") (pin "P$AC21") (pinfunction "P0.25_P$AC21") (pintype "bidirectional"))
    )
    (net (code "81") (name "P0.26") (class "Default")
      (node (ref "U1") (pin "P$G1") (pinfunction "P0.26_P$G1") (pintype "bidirectional"))
    )
    (net (code "82") (name "P0.27") (class "Default")
      (node (ref "U1") (pin "P$H2") (pinfunction "P0.27_P$H2") (pintype "bidirectional"))
    )
    (net (code "83") (name "P0.28") (class "Default")
      (node (ref "U1") (pin "P$B11") (pinfunction "P0.28/AIN4_P$B11") (pintype "bidirectional"))
    )
    (net (code "84") (name "P0.29") (class "Default")
      (node (ref "U1") (pin "P$A10") (pinfunction "P0.29/AIN5_P$A10") (pintype "bidirectional"))
    )
    (net (code "85") (name "P0.30") (class "Default")
      (node (ref "U1") (pin "P$B9") (pinfunction "P0.30/AIN6_P$B9") (pintype "bidirectional"))
    )
    (net (code "86") (name "P0.31") (class "Default")
      (node (ref "U1") (pin "P$A8") (pinfunction "P0.31/AIN7_P$A8") (pintype "bidirectional"))
    )
    (net (code "87") (name "P1.01{slash}1.6C") (class "Default")
      (node (ref "DMG2305UX-7") (pin "1") (pinfunction "G_1") (pintype "bidirectional"))
      (node (ref "R_PWR_EPD") (pin "1") (pinfunction "1_1") (pintype "bidirectional"))
    )
    (net (code "88") (name "P1.01{slash}2.4B") (class "Default")
      (node (ref "U1") (pin "P$Y23") (pinfunction "P1.01_P$Y23") (pintype "bidirectional"))
    )
    (net (code "89") (name "P1.02{slash}1.6C") (class "Default")
      (node (ref "SW_DN") (pin "2") (pinfunction "2_2") (pintype "passive"))
    )
    (net (code "90") (name "P1.02{slash}2.8C") (class "Default")
      (node (ref "U1") (pin "P$W24") (pinfunction "P1.02_P$W24") (pintype "bidirectional"))
    )
    (net (code "91") (name "P1.03") (class "Default")
      (node (ref "U1") (pin "P$V23") (pinfunction "P1.03_P$V23") (pintype "bidirectional"))
    )
    (net (code "92") (name "P1.04") (class "Default")
      (node (ref "U1") (pin "P$U24") (pinfunction "P1.04_P$U24") (pintype "bidirectional"))
    )
    (net (code "93") (name "P1.05") (class "Default")
      (node (ref "U1") (pin "P$T23") (pinfunction "P1.05_P$T23") (pintype "bidirectional"))
    )
    (net (code "94") (name "P1.06") (class "Default")
      (node (ref "U1") (pin "P$R24") (pinfunction "P1.06_P$R24") (pintype "bidirectional"))
    )
    (net (code "95") (name "P1.07") (class "Default")
      (node (ref "U1") (pin "P$P23") (pinfunction "P1.07_P$P23") (pintype "bidirectional"))
    )
    (net (code "96") (name "P1.09") (class "Default")
      (node (ref "U1") (pin "P$R1") (pinfunction "P1.09_P$R1") (pintype "bidirectional"))
    )
    (net (code "97") (name "P1.10") (class "Default")
      (node (ref "U1") (pin "P$A20") (pinfunction "P1.10_P$A20") (pintype "bidirectional"))
    )
    (net (code "98") (name "P1.11") (class "Default")
      (node (ref "U1") (pin "P$B19") (pinfunction "P1.11_P$B19") (pintype "bidirectional"))
    )
    (net (code "99") (name "P1.12") (class "Default")
      (node (ref "U1") (pin "P$B17") (pinfunction "P1.12_P$B17") (pintype "bidirectional"))
    )
    (net (code "100") (name "P1.13") (class "Default")
      (node (ref "U1") (pin "P$A16") (pinfunction "P1.13_P$A16") (pintype "bidirectional"))
    )
    (net (code "101") (name "P1.14") (class "Default")
      (node (ref "U1") (pin "P$B15") (pinfunction "P1.14_P$B15") (pintype "bidirectional"))
    )
    (net (code "102") (name "P1.15") (class "Default")
      (node (ref "U1") (pin "P$A14") (pinfunction "P1.15_P$A14") (pintype "bidirectional"))
    )
    (net (code "103") (name "PMIC_INT") (class "Default")
      (node (ref "IC1") (pin "A1") (pinfunction "~{INT}_A1") (pintype "bidirectional"))
      (node (ref "U1") (pin "P$T2") (pinfunction "P0.11_P$T2") (pintype "bidirectional"))
    )
    (net (code "104") (name "PREVGH") (class "Default")
      (node (ref "D5") (pin "1") (pinfunction "K_1") (pintype "bidirectional"))
      (node (ref "EPD_C9") (pin "2") (pinfunction "2_2") (pintype "passive"))
      (node (ref "J1") (pin "21") (pinfunction "21_21") (pintype "bidirectional"))
    )
    (net (code "105") (name "PREVGL") (class "Default")
      (node (ref "D2") (pin "2") (pinfunction "A_2") (pintype "bidirectional"))
      (node (ref "EPD_C11") (pin "2") (pinfunction "2_2") (pintype "passive"))
      (node (ref "J1") (pin "23") (pinfunction "23_23") (pintype "bidirectional"))
    )
    (net (code "106") (name "RESE") (class "Default")
      (node (ref "J1") (pin "3") (pinfunction "3_3") (pintype "bidirectional"))
      (node (ref "Q3") (pin "2") (pinfunction "S_2") (pintype "bidirectional"))
      (node (ref "R1_EP_DR") (pin "2") (pinfunction "2_2") (pintype "bidirectional"))
    )
    (net (code "107") (name "RESET") (class "Default")
      (node (ref "J2") (pin "6") (pinfunction "6_6") (pintype "bidirectional"))
      (node (ref "TP_RESET") (pin "TP") (pinfunction "TP_TP") (pintype "input"))
      (node (ref "U1") (pin "P$AC13") (pinfunction "P0.18/RESET_P$AC13") (pintype "bidirectional"))
    )
    (net (code "108") (name "SCK{slash}1.5B") (class "Default")
      (node (ref "J1") (pin "13") (pinfunction "13_13") (pintype "bidirectional"))
    )
    (net (code "109") (name "SCK{slash}2.2D") (class "Default")
      (node (ref "U1") (pin "P$A12") (pinfunction "P0.02/AIN0_P$A12") (pintype "bidirectional"))
    )
    (net (code "110") (name "SCL{slash}1.4C") (class "Default")
      (node (ref "IC2") (pin "C1") (pinfunction "SCL_C1") (pintype "bidirectional"))
      (node (ref "U3") (pin "7") (pinfunction "SCL_7") (pintype "input"))
    )
    (net (code "111") (name "SCL{slash}2.4C") (class "Default")
      (node (ref "IC1") (pin "B1") (pinfunction "SCL_B1") (pintype "bidirectional"))
      (node (ref "IC3") (pin "12") (pinfunction "SCX_12") (pintype "bidirectional"))
      (node (ref "R17") (pin "2") (pinfunction "2_2") (pintype "bidirectional"))
      (node (ref "R4") (pin "1") (pinfunction "1_1") (pintype "bidirectional"))
      (node (ref "TP_SCL") (pin "TP") (pinfunction "TP_TP") (pintype "input"))
      (node (ref "U1") (pin "P$M2") (pinfunction "P0.07_P$M2") (pintype "bidirectional"))
    )
    (net (code "112") (name "SDA{slash}1.4C") (class "Default")
      (node (ref "IC2") (pin "B2") (pinfunction "SDA_B2") (pintype "bidirectional"))
      (node (ref "U3") (pin "8") (pinfunction "SDA_8") (pintype "bidirectional"))
    )
    (net (code "113") (name "SDA{slash}2.4C") (class "Default")
      (node (ref "IC1") (pin "C1") (pinfunction "SDA_C1") (pintype "bidirectional"))
      (node (ref "IC3") (pin "2") (pinfunction "SDX_2") (pintype "bidirectional"))
      (node (ref "R18") (pin "2") (pinfunction "2_2") (pintype "bidirectional"))
      (node (ref "R2") (pin "1") (pinfunction "1_1") (pintype "bidirectional"))
      (node (ref "TP_SDA") (pin "TP") (pinfunction "TP_TP") (pintype "input"))
      (node (ref "U1") (pin "P$L1") (pinfunction "P0.06_P$L1") (pintype "bidirectional"))
    )
    (net (code "114") (name "SWDCLK") (class "Default")
      (node (ref "J2") (pin "4") (pinfunction "4_4") (pintype "bidirectional"))
      (node (ref "TP_SWDCLK") (pin "TP") (pinfunction "TP_TP") (pintype "input"))
      (node (ref "U1") (pin "P$AA24") (pinfunction "SWDCLK_P$AA24") (pintype "input"))
    )
    (net (code "115") (name "SWDIO") (class "Default")
      (node (ref "J2") (pin "2") (pinfunction "2_2") (pintype "bidirectional"))
      (node (ref "TP_SWDIO") (pin "TP") (pinfunction "TP_TP") (pintype "input"))
      (node (ref "U1") (pin "P$AC24") (pinfunction "SWDIO_P$AC24") (pintype "bidirectional"))
    )
    (net (code "116") (name "SWO") (class "Default")
      (node (ref "TP_SWO") (pin "TP") (pinfunction "TP_TP") (pintype "input"))
      (node (ref "U1") (pin "P$AD22") (pinfunction "P1.00_P$AD22") (pintype "bidirectional"))
    )
    (net (code "117") (name "VBAT{slash}1.2A") (class "Default")
      (node (ref "C27") (pin "2") (pinfunction "2_2") (pintype "passive"))
      (node (ref "TP_VBAT") (pin "TP") (pinfunction "TP_TP") (pintype "input"))
      (node (ref "U3") (pin "2") (pinfunction "CELL_2") (pintype "power_in"))
      (node (ref "U3") (pin "3") (pinfunction "VDD_3") (pintype "power_in"))
    )
    (net (code "118") (name "VBAT{slash}2.5C") (class "Default")
      (node (ref "C37") (pin "2") (pinfunction "2_2") (pintype "passive"))
      (node (ref "IC1") (pin "C2") (pinfunction "BAT_C2") (pintype "bidirectional"))
    )
    (net (code "119") (name "VBUS{slash}1.5D") (class "Default")
      (node (ref "C42") (pin "1") (pinfunction "1_1") (pintype "passive"))
      (node (ref "C43") (pin "1") (pinfunction "1_1") (pintype "passive"))
      (node (ref "D3") (pin "5") (pinfunction "VBUS_5") (pintype "bidirectional"))
      (node (ref "J4") (pin "A4_B9") (pinfunction "VBUS_A4_B9") (pintype "power_in"))
      (node (ref "J4") (pin "A9_B4") (pinfunction "VBUS_A9_B4") (pintype "power_in"))
    )
    (net (code "120") (name "VBUS{slash}2.6D") (class "Default")
      (node (ref "C21") (pin "1") (pinfunction "1_1") (pintype "passive"))
      (node (ref "C38") (pin "2") (pinfunction "2_2") (pintype "passive"))
      (node (ref "IC1") (pin "A2") (pinfunction "IN_A2") (pintype "bidirectional"))
      (node (ref "U1") (pin "P$AD2") (pinfunction "VBUS_P$AD2") (pintype "power_in"))
    )
    (net (code "121") (name "VREG") (class "Default")
      (node (ref "C23") (pin "1") (pinfunction "1_1") (pintype "passive"))
      (node (ref "C24") (pin "2") (pinfunction "2_2") (pintype "passive"))
      (node (ref "C39") (pin "1") (pinfunction "1_1") (pintype "passive"))
      (node (ref "IC1") (pin "B2") (pinfunction "SYS_B2") (pintype "bidirectional"))
      (node (ref "IC9") (pin "A1") (pinfunction "EN_A1") (pintype "bidirectional"))
      (node (ref "IC9") (pin "A2") (pinfunction "VIN_1_A2") (pintype "bidirectional"))
      (node (ref "IC9") (pin "A3") (pinfunction "VIN_2_A3") (pintype "bidirectional"))
      (node (ref "TP_VREG") (pin "TP") (pinfunction "TP_TP") (pintype "input"))
    )
    (net (code "122") (name "unconnected-(ANT1-NC-Pad2)") (class "Default")
      (node (ref "ANT1") (pin "2") (pinfunction "NC_2") (pintype "no_connect"))
    )
    (net (code "123") (name "unconnected-(C27-Pad1)") (class "Default")
      (node (ref "C27") (pin "1") (pinfunction "1_1") (pintype "passive"))
    )
    (net (code "124") (name "unconnected-(EPD_C1-Pad1)") (class "Default")
      (node (ref "EPD_C1") (pin "1") (pinfunction "1_1") (pintype "passive"))
    )
    (net (code "125") (name "unconnected-(EPD_C2-Pad1)") (class "Default")
      (node (ref "EPD_C2") (pin "1") (pinfunction "1_1") (pintype "passive"))
    )
    (net (code "126") (name "unconnected-(IC3-ASCL-Pad11)") (class "Default")
      (node (ref "IC3") (pin "11") (pinfunction "ASCL_11") (pintype "bidirectional"))
    )
    (net (code "127") (name "unconnected-(IC3-ASDA-Pad4)") (class "Default")
      (node (ref "IC3") (pin "4") (pinfunction "ASDA_4") (pintype "bidirectional"))
    )
    (net (code "128") (name "unconnected-(J1-Pad1)") (class "Default")
      (node (ref "J1") (pin "1") (pinfunction "1_1") (pintype "bidirectional"))
    )
    (net (code "129") (name "unconnected-(J1-Pad6)") (class "Default")
      (node (ref "J1") (pin "6") (pinfunction "6_6") (pintype "bidirectional"))
    )
    (net (code "130") (name "unconnected-(J1-Pad7)") (class "Default")
      (node (ref "J1") (pin "7") (pinfunction "7_7") (pintype "bidirectional"))
    )
    (net (code "131") (name "unconnected-(J1-PadMP2)") (class "Default")
      (node (ref "J1") (pin "MP2") (pinfunction "MP2_MP2") (pintype "bidirectional"))
    )
    (net (code "132") (name "unconnected-(J4-SBU1-PadA8)") (class "Default")
      (node (ref "J4") (pin "A8") (pinfunction "SBU1_A8") (pintype "bidirectional"))
    )
    (net (code "133") (name "unconnected-(J4-SBU2-PadB8)") (class "Default")
      (node (ref "J4") (pin "B8") (pinfunction "SBU2_B8") (pintype "bidirectional"))
    )
    (net (code "134") (name "unconnected-(U1-DCCH-PadP$AB2)") (class "Default")
      (node (ref "U1") (pin "P$AB2") (pinfunction "DCCH_P$AB2") (pintype "bidirectional"))
    )
  )
)
